# Main.net
KiCad netlist of a schematic drawn in Altium Designer
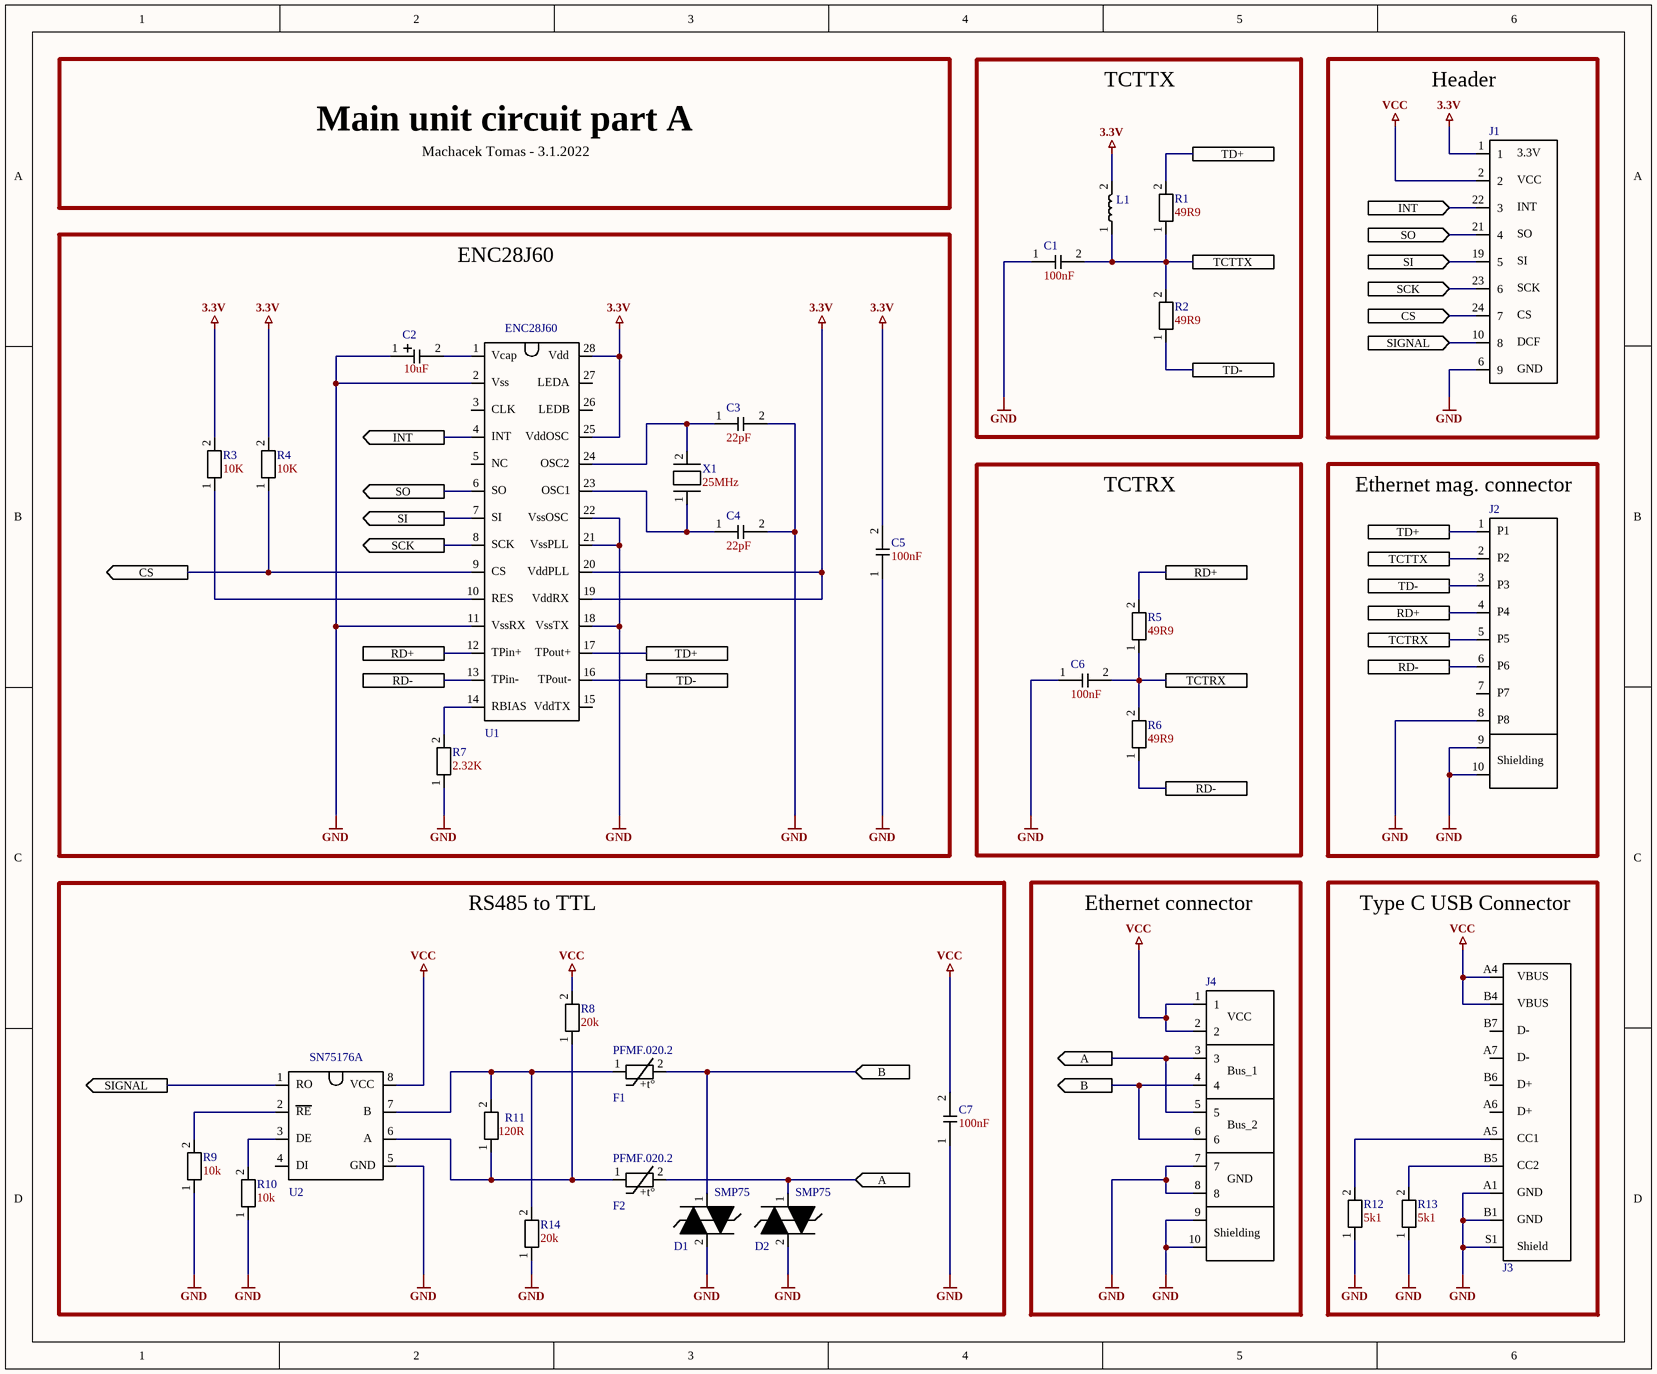
[diagram p0: Main.SchDoc]

(export (version "E")
  (design (tool "Eeschema 10.0.6"))
  (components
    (comp (ref "C1")
      (value "100nF")
      (footprint "MLCC_capacitator")
      (description "MLCC capacitator - 1206")
      (fields (field (name "Comment") "Capacitator_MLCC"))
      (libsource (lib "Schematic_library") (part "Capacitator_MLCC"))
    )
    (comp (ref "C2")
      (value "10uF")
      (footprint "Tantalum_capacitor")
      (description "Aluminum capacitator - filtration")
      (fields (field (name "Comment") "Capacitator_aluminium"))
      (libsource (lib "Schematic_library") (part "Capacitator_aluminium"))
    )
    (comp (ref "C3")
      (value "22pF")
      (footprint "MLCC_capacitator")
      (description "MLCC capacitator - 1206")
      (fields (field (name "Comment") "Capacitator_MLCC"))
      (libsource (lib "Schematic_library") (part "Capacitator_MLCC"))
    )
    (comp (ref "C4")
      (value "22pF")
      (footprint "MLCC_capacitator")
      (description "MLCC capacitator - 1206")
      (fields (field (name "Comment") "Capacitator_MLCC"))
      (libsource (lib "Schematic_library") (part "Capacitator_MLCC"))
    )
    (comp (ref "C5")
      (value "100nF")
      (footprint "MLCC_capacitator")
      (description "MLCC capacitator - 1206")
      (fields (field (name "Comment") "Capacitator_MLCC"))
      (libsource (lib "Schematic_library") (part "Capacitator_MLCC"))
    )
    (comp (ref "C6")
      (value "100nF")
      (footprint "MLCC_capacitator")
      (description "MLCC capacitator - 1206")
      (fields (field (name "Comment") "Capacitator_MLCC"))
      (libsource (lib "Schematic_library") (part "Capacitator_MLCC"))
    )
    (comp (ref "C7")
      (value "100nF")
      (footprint "MLCC_capacitator")
      (description "MLCC capacitator - 1206")
      (fields (field (name "Comment") "Capacitator_MLCC"))
      (libsource (lib "Schematic_library") (part "Capacitator_MLCC"))
    )
    (comp (ref "D1")
      (value "SMP75")
      (footprint "SMP75")
      (description "Bidirectional crowbar protection")
      (libsource (lib "Schematic_library") (part "SMP75"))
    )
    (comp (ref "D2")
      (value "SMP75")
      (footprint "SMP75")
      (description "Bidirectional crowbar protection")
      (libsource (lib "Schematic_library") (part "SMP75"))
    )
    (comp (ref "F1")
      (value "PFMF.020.2")
      (footprint "PFMF.020.2")
      (description "SMD fuse")
      (libsource (lib "Schematic_library") (part "PFMF.020.2"))
    )
    (comp (ref "F2")
      (value "PFMF.020.2")
      (footprint "PFMF.020.2")
      (description "SMD fuse")
      (libsource (lib "Schematic_library") (part "PFMF.020.2"))
    )
    (comp (ref "J1")
      (value "20x2_header")
      (footprint "20x2_Header")
      (description "40 position pin header")
      (libsource (lib "Schematic_library") (part "20x2_header"))
    )
    (comp (ref "J2")
      (value "Ethernet_mag_connector")
      (footprint "Ethernet_mag_connector")
      (description "Ethernet magnetic connector")
      (libsource (lib "Schematic_library") (part "Ethernet_mag_connector"))
    )
    (comp (ref "J3")
      (value "USB_C_connector")
      (footprint "Usb_c_right_angle")
      (description "USB type C")
      (libsource (lib "Schematic_library") (part "USB_C_connector"))
    )
    (comp (ref "J4")
      (value "Ethernet_connector")
      (footprint "Ethernet_connector")
      (description "Ethernet connector")
      (libsource (lib "Schematic_library") (part "Ethernet_connector"))
    )
    (comp (ref "L1")
      (value "Ferrite_bead")
      (footprint "Ferrite_bead")
      (description "Multilayer Ferrite Bead")
      (libsource (lib "Schematic_library") (part "Ferrite_bead"))
    )
    (comp (ref "R1")
      (value "49R9")
      (footprint "Resistor")
      (description "SMD resistor - 1206")
      (fields (field (name "Comment") "Resistor"))
      (libsource (lib "Schematic_library") (part "Resistor"))
    )
    (comp (ref "R2")
      (value "49R9")
      (footprint "Resistor")
      (description "SMD resistor - 1206")
      (fields (field (name "Comment") "Resistor"))
      (libsource (lib "Schematic_library") (part "Resistor"))
    )
    (comp (ref "R3")
      (value "10K")
      (footprint "Resistor")
      (description "SMD resistor - 1206")
      (fields (field (name "Comment") "Resistor"))
      (libsource (lib "Schematic_library") (part "Resistor"))
    )
    (comp (ref "R4")
      (value "10K")
      (footprint "Resistor")
      (description "SMD resistor - 1206")
      (fields (field (name "Comment") "Resistor"))
      (libsource (lib "Schematic_library") (part "Resistor"))
    )
    (comp (ref "R5")
      (value "49R9")
      (footprint "Resistor")
      (description "SMD resistor - 1206")
      (fields (field (name "Comment") "Resistor"))
      (libsource (lib "Schematic_library") (part "Resistor"))
    )
    (comp (ref "R6")
      (value "49R9")
      (footprint "Resistor")
      (description "SMD resistor - 1206")
      (fields (field (name "Comment") "Resistor"))
      (libsource (lib "Schematic_library") (part "Resistor"))
    )
    (comp (ref "R7")
      (value "2.32K")
      (footprint "Resistor")
      (description "SMD resistor - 1206")
      (fields (field (name "Comment") "Resistor"))
      (libsource (lib "Schematic_library") (part "Resistor"))
    )
    (comp (ref "R8")
      (value "20k")
      (footprint "Resistor")
      (description "SMD resistor - 1206")
      (fields (field (name "Comment") "Resistor"))
      (libsource (lib "Schematic_library") (part "Resistor"))
    )
    (comp (ref "R9")
      (value "10k")
      (footprint "Resistor")
      (description "SMD resistor - 1206")
      (fields (field (name "Comment") "Resistor"))
      (libsource (lib "Schematic_library") (part "Resistor"))
    )
    (comp (ref "R10")
      (value "10k")
      (footprint "Resistor")
      (description "SMD resistor - 1206")
      (fields (field (name "Comment") "Resistor"))
      (libsource (lib "Schematic_library") (part "Resistor"))
    )
    (comp (ref "R11")
      (value "120R")
      (footprint "Resistor")
      (description "SMD resistor - 1206")
      (fields (field (name "Comment") "Resistor"))
      (libsource (lib "Schematic_library") (part "Resistor"))
    )
    (comp (ref "R12")
      (value "5k1")
      (footprint "Resistor")
      (description "SMD resistor - 1206")
      (fields (field (name "Comment") "Resistor"))
      (libsource (lib "Schematic_library") (part "Resistor"))
    )
    (comp (ref "R13")
      (value "5k1")
      (footprint "Resistor")
      (description "SMD resistor - 1206")
      (fields (field (name "Comment") "Resistor"))
      (libsource (lib "Schematic_library") (part "Resistor"))
    )
    (comp (ref "R14")
      (value "20k")
      (footprint "Resistor")
      (description "SMD resistor - 1206")
      (fields (field (name "Comment") "Resistor"))
      (libsource (lib "Schematic_library") (part "Resistor"))
    )
    (comp (ref "U1")
      (value "ENC28J60")
      (footprint "ENC28J60")
      (description "Stand-Alone Ethernet Controller with SPI Interface")
      (libsource (lib "Schematic_library") (part "ENC28J60"))
    )
    (comp (ref "U2")
      (value "SN75176A")
      (footprint "SN75176A")
      (description "RS485 transreciever")
      (libsource (lib "Schematic_library") (part "SN75176A"))
    )
    (comp (ref "X1")
      (value "25MHz")
      (footprint "Crystal_25MHz")
      (description "Quartz crystal 25MHz")
      (fields (field (name "Comment") "Crystal_1"))
      (libsource (lib "Schematic_library") (part "Crystal_1"))
    )
  )
  (nets
    (net (code "1") (name "/A") (class "Default")
      (node (ref "D2") (pin "1") (pinfunction "1_1") (pintype "passive"))
      (node (ref "F2") (pin "2") (pinfunction "2_2") (pintype "passive"))
      (node (ref "J4") (pin "3") (pinfunction "3_3") (pintype "passive"))
      (node (ref "J4") (pin "5") (pinfunction "5_5") (pintype "passive"))
    )
    (net (code "2") (name "/B") (class "Default")
      (node (ref "D1") (pin "1") (pinfunction "1_1") (pintype "passive"))
      (node (ref "F1") (pin "2") (pinfunction "2_2") (pintype "passive"))
      (node (ref "J4") (pin "4") (pinfunction "4_4") (pintype "passive"))
      (node (ref "J4") (pin "6") (pinfunction "6_6") (pintype "passive"))
    )
    (net (code "3") (name "/CS") (class "Default")
      (node (ref "J1") (pin "24") (pinfunction "7_24") (pintype "passive"))
      (node (ref "R4") (pin "1") (pinfunction "1_1") (pintype "passive"))
      (node (ref "U1") (pin "9") (pinfunction "9_9") (pintype "passive"))
    )
    (net (code "4") (name "/INT") (class "Default")
      (node (ref "J1") (pin "22") (pinfunction "3_22") (pintype "passive"))
      (node (ref "U1") (pin "4") (pinfunction "4_4") (pintype "passive"))
    )
    (net (code "5") (name "/RD+") (class "Default")
      (node (ref "J2") (pin "4") (pinfunction "4_4") (pintype "passive"))
      (node (ref "R5") (pin "2") (pinfunction "2_2") (pintype "passive"))
      (node (ref "U1") (pin "12") (pinfunction "12_12") (pintype "passive"))
    )
    (net (code "6") (name "/RD-") (class "Default")
      (node (ref "J2") (pin "6") (pinfunction "6_6") (pintype "passive"))
      (node (ref "R6") (pin "1") (pinfunction "1_1") (pintype "passive"))
      (node (ref "U1") (pin "13") (pinfunction "13_13") (pintype "passive"))
    )
    (net (code "7") (name "/SCK") (class "Default")
      (node (ref "J1") (pin "23") (pinfunction "6_23") (pintype "passive"))
      (node (ref "U1") (pin "8") (pinfunction "8_8") (pintype "passive"))
    )
    (net (code "8") (name "/SI") (class "Default")
      (node (ref "J1") (pin "19") (pinfunction "5_19") (pintype "passive"))
      (node (ref "U1") (pin "7") (pinfunction "7_7") (pintype "passive"))
    )
    (net (code "9") (name "/SIGNAL") (class "Default")
      (node (ref "J1") (pin "10") (pinfunction "8_10") (pintype "passive"))
      (node (ref "U2") (pin "1") (pinfunction "1_1") (pintype "passive"))
    )
    (net (code "10") (name "/SO") (class "Default")
      (node (ref "J1") (pin "21") (pinfunction "4_21") (pintype "passive"))
      (node (ref "U1") (pin "6") (pinfunction "6_6") (pintype "passive"))
    )
    (net (code "11") (name "/TCTRX") (class "Default")
      (node (ref "C6") (pin "2") (pinfunction "2_2") (pintype "passive"))
      (node (ref "J2") (pin "5") (pinfunction "5_5") (pintype "passive"))
      (node (ref "R5") (pin "1") (pinfunction "1_1") (pintype "passive"))
      (node (ref "R6") (pin "2") (pinfunction "2_2") (pintype "passive"))
    )
    (net (code "12") (name "/TCTTX") (class "Default")
      (node (ref "C1") (pin "2") (pinfunction "2_2") (pintype "passive"))
      (node (ref "J2") (pin "2") (pinfunction "2_2") (pintype "passive"))
      (node (ref "L1") (pin "1") (pinfunction "1_1") (pintype "passive"))
      (node (ref "R1") (pin "1") (pinfunction "1_1") (pintype "passive"))
      (node (ref "R2") (pin "2") (pinfunction "2_2") (pintype "passive"))
    )
    (net (code "13") (name "/TD+") (class "Default")
      (node (ref "J2") (pin "1") (pinfunction "1_1") (pintype "passive"))
      (node (ref "R1") (pin "2") (pinfunction "2_2") (pintype "passive"))
      (node (ref "U1") (pin "17") (pinfunction "17_17") (pintype "passive"))
    )
    (net (code "14") (name "/TD-") (class "Default")
      (node (ref "J2") (pin "3") (pinfunction "3_3") (pintype "passive"))
      (node (ref "R2") (pin "1") (pinfunction "1_1") (pintype "passive"))
      (node (ref "U1") (pin "16") (pinfunction "16_16") (pintype "passive"))
    )
    (net (code "15") (name "3.3V") (class "Default")
      (node (ref "C5") (pin "2") (pinfunction "2_2") (pintype "passive"))
      (node (ref "J1") (pin "1") (pinfunction "1_1") (pintype "passive"))
      (node (ref "L1") (pin "2") (pinfunction "2_2") (pintype "passive"))
      (node (ref "R3") (pin "2") (pinfunction "2_2") (pintype "passive"))
      (node (ref "R4") (pin "2") (pinfunction "2_2") (pintype "passive"))
      (node (ref "U1") (pin "19") (pinfunction "19_19") (pintype "passive"))
      (node (ref "U1") (pin "20") (pinfunction "20_20") (pintype "passive"))
      (node (ref "U1") (pin "25") (pinfunction "25_25") (pintype "passive"))
      (node (ref "U1") (pin "28") (pinfunction "28_28") (pintype "passive"))
    )
    (net (code "16") (name "GND") (class "Default")
      (node (ref "C1") (pin "1") (pinfunction "1_1") (pintype "passive"))
      (node (ref "C2") (pin "1") (pinfunction "1_1") (pintype "passive"))
      (node (ref "C3") (pin "2") (pinfunction "2_2") (pintype "passive"))
      (node (ref "C4") (pin "2") (pinfunction "2_2") (pintype "passive"))
      (node (ref "C5") (pin "1") (pinfunction "1_1") (pintype "passive"))
      (node (ref "C6") (pin "1") (pinfunction "1_1") (pintype "passive"))
      (node (ref "C7") (pin "1") (pinfunction "1_1") (pintype "passive"))
      (node (ref "D1") (pin "2") (pinfunction "2_2") (pintype "passive"))
      (node (ref "D2") (pin "2") (pinfunction "2_2") (pintype "passive"))
      (node (ref "J1") (pin "6") (pinfunction "9_6") (pintype "passive"))
      (node (ref "J2") (pin "10") (pinfunction "10_10") (pintype "passive"))
      (node (ref "J2") (pin "8") (pinfunction "8_8") (pintype "passive"))
      (node (ref "J2") (pin "9") (pinfunction "9_9") (pintype "passive"))
      (node (ref "J3") (pin "A1") (pinfunction "A1_A1") (pintype "passive"))
      (node (ref "J3") (pin "B1") (pinfunction "B1_B1") (pintype "passive"))
      (node (ref "J3") (pin "S1") (pinfunction "S1_S1") (pintype "passive"))
      (node (ref "J4") (pin "10") (pinfunction "10_10") (pintype "passive"))
      (node (ref "J4") (pin "7") (pinfunction "7_7") (pintype "passive"))
      (node (ref "J4") (pin "8") (pinfunction "8_8") (pintype "passive"))
      (node (ref "J4") (pin "9") (pinfunction "9_9") (pintype "passive"))
      (node (ref "R10") (pin "1") (pinfunction "1_1") (pintype "passive"))
      (node (ref "R12") (pin "1") (pinfunction "1_1") (pintype "passive"))
      (node (ref "R13") (pin "1") (pinfunction "1_1") (pintype "passive"))
      (node (ref "R14") (pin "1") (pinfunction "1_1") (pintype "passive"))
      (node (ref "R7") (pin "1") (pinfunction "1_1") (pintype "passive"))
      (node (ref "R9") (pin "1") (pinfunction "1_1") (pintype "passive"))
      (node (ref "U1") (pin "11") (pinfunction "11_11") (pintype "passive"))
      (node (ref "U1") (pin "18") (pinfunction "18_18") (pintype "passive"))
      (node (ref "U1") (pin "2") (pinfunction "2_2") (pintype "passive"))
      (node (ref "U1") (pin "21") (pinfunction "21_21") (pintype "passive"))
      (node (ref "U1") (pin "22") (pinfunction "22_22") (pintype "passive"))
      (node (ref "U2") (pin "5") (pinfunction "5_5") (pintype "passive"))
    )
    (net (code "17") (name "Net-(C2-Pad2)") (class "Default")
      (node (ref "C2") (pin "2") (pinfunction "2_2") (pintype "passive"))
      (node (ref "U1") (pin "1") (pinfunction "1_1") (pintype "passive"))
    )
    (net (code "18") (name "Net-(C3-Pad1)") (class "Default")
      (node (ref "C3") (pin "1") (pinfunction "1_1") (pintype "passive"))
      (node (ref "U1") (pin "24") (pinfunction "24_24") (pintype "passive"))
      (node (ref "X1") (pin "2") (pinfunction "2_2") (pintype "passive"))
    )
    (net (code "19") (name "Net-(C4-Pad1)") (class "Default")
      (node (ref "C4") (pin "1") (pinfunction "1_1") (pintype "passive"))
      (node (ref "U1") (pin "23") (pinfunction "23_23") (pintype "passive"))
      (node (ref "X1") (pin "1") (pinfunction "1_1") (pintype "passive"))
    )
    (net (code "20") (name "Net-(F1-Pad1)") (class "Default")
      (node (ref "F1") (pin "1") (pinfunction "1_1") (pintype "passive"))
      (node (ref "R11") (pin "2") (pinfunction "2_2") (pintype "passive"))
      (node (ref "R14") (pin "2") (pinfunction "2_2") (pintype "passive"))
      (node (ref "U2") (pin "7") (pinfunction "7_7") (pintype "passive"))
    )
    (net (code "21") (name "Net-(F2-Pad1)") (class "Default")
      (node (ref "F2") (pin "1") (pinfunction "1_1") (pintype "passive"))
      (node (ref "R11") (pin "1") (pinfunction "1_1") (pintype "passive"))
      (node (ref "R8") (pin "1") (pinfunction "1_1") (pintype "passive"))
      (node (ref "U2") (pin "6") (pinfunction "6_6") (pintype "passive"))
    )
    (net (code "22") (name "Net-(J3-PadA5)") (class "Default")
      (node (ref "J3") (pin "A5") (pinfunction "A5_A5") (pintype "passive"))
      (node (ref "R12") (pin "2") (pinfunction "2_2") (pintype "passive"))
    )
    (net (code "23") (name "Net-(J3-PadB5)") (class "Default")
      (node (ref "J3") (pin "B5") (pinfunction "B5_B5") (pintype "passive"))
      (node (ref "R13") (pin "2") (pinfunction "2_2") (pintype "passive"))
    )
    (net (code "24") (name "Net-(R3-Pad1)") (class "Default")
      (node (ref "R3") (pin "1") (pinfunction "1_1") (pintype "passive"))
      (node (ref "U1") (pin "10") (pinfunction "10_10") (pintype "passive"))
    )
    (net (code "25") (name "Net-(R7-Pad2)") (class "Default")
      (node (ref "R7") (pin "2") (pinfunction "2_2") (pintype "passive"))
      (node (ref "U1") (pin "14") (pinfunction "14_14") (pintype "passive"))
    )
    (net (code "26") (name "Net-(R9-Pad2)") (class "Default")
      (node (ref "R9") (pin "2") (pinfunction "2_2") (pintype "passive"))
      (node (ref "U2") (pin "2") (pinfunction "2_2") (pintype "passive"))
    )
    (net (code "27") (name "Net-(R10-Pad2)") (class "Default")
      (node (ref "R10") (pin "2") (pinfunction "2_2") (pintype "passive"))
      (node (ref "U2") (pin "3") (pinfunction "3_3") (pintype "passive"))
    )
    (net (code "28") (name "VCC") (class "Default")
      (node (ref "C7") (pin "2") (pinfunction "2_2") (pintype "passive"))
      (node (ref "J1") (pin "2") (pinfunction "2_2") (pintype "passive"))
      (node (ref "J3") (pin "A4") (pinfunction "A4_A4") (pintype "passive"))
      (node (ref "J3") (pin "B4") (pinfunction "B4_B4") (pintype "passive"))
      (node (ref "J4") (pin "1") (pinfunction "1_1") (pintype "passive"))
      (node (ref "J4") (pin "2") (pinfunction "2_2") (pintype "passive"))
      (node (ref "R8") (pin "2") (pinfunction "2_2") (pintype "passive"))
      (node (ref "U2") (pin "8") (pinfunction "8_8") (pintype "passive"))
    )
    (net (code "29") (name "unconnected-(J2-Pad7)") (class "Default")
      (node (ref "J2") (pin "7") (pinfunction "7_7") (pintype "passive"))
    )
    (net (code "30") (name "unconnected-(J3-PadA6)") (class "Default")
      (node (ref "J3") (pin "A6") (pinfunction "A6_A6") (pintype "passive"))
    )
    (net (code "31") (name "unconnected-(J3-PadA7)") (class "Default")
      (node (ref "J3") (pin "A7") (pinfunction "A7_A7") (pintype "passive"))
    )
    (net (code "32") (name "unconnected-(J3-PadB6)") (class "Default")
      (node (ref "J3") (pin "B6") (pinfunction "B6_B6") (pintype "passive"))
    )
    (net (code "33") (name "unconnected-(J3-PadB7)") (class "Default")
      (node (ref "J3") (pin "B7") (pinfunction "B7_B7") (pintype "passive"))
    )
    (net (code "34") (name "unconnected-(U1-Pad3)") (class "Default")
      (node (ref "U1") (pin "3") (pinfunction "3_3") (pintype "passive"))
    )
    (net (code "35") (name "unconnected-(U1-Pad5)") (class "Default")
      (node (ref "U1") (pin "5") (pinfunction "5_5") (pintype "passive"))
    )
    (net (code "36") (name "unconnected-(U1-Pad15)") (class "Default")
      (node (ref "U1") (pin "15") (pinfunction "15_15") (pintype "passive"))
    )
    (net (code "37") (name "unconnected-(U1-Pad26)") (class "Default")
      (node (ref "U1") (pin "26") (pinfunction "26_26") (pintype "passive"))
    )
    (net (code "38") (name "unconnected-(U1-Pad27)") (class "Default")
      (node (ref "U1") (pin "27") (pinfunction "27_27") (pintype "passive"))
    )
    (net (code "39") (name "unconnected-(U2-Pad4)") (class "Default")
      (node (ref "U2") (pin "4") (pinfunction "4_4") (pintype "passive"))
    )
  )
)
